# DC-DC_5V0_To_3V3.net
KiCad netlist of a schematic drawn in Altium Designer
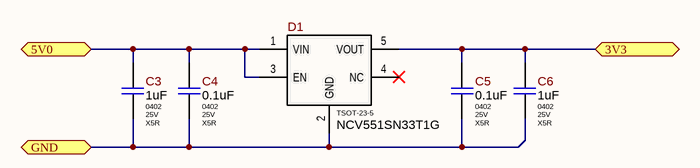
[diagram p0: DC-DC_5V0_To_3V3.SchDoc]

(export (version "E")
  (design (tool "Eeschema 10.0.6"))
  (components
    (comp (ref "C3")
      (value "1uF")
      (footprint "C_CERAMIC_0402_MED")
      (description "1uF 25V Х5R ±10% 0402 Ceramic Capacitor RoHS")
      (fields
        (field (name "PACKAGE") "0402")
        (field (name "VOLTAGE") "25V")
        (field (name "DIELECTRIC TYPE") "X5R")
        (field (name "PART NUMBER") "GRM155R61E105KA12D")
        (field (name "MANUFACTURER") "Murata Electronics")
      )
      (libsource (lib "EL.XXX.T01") (part "Capacitor-NonPolar"))
    )
    (comp (ref "C4")
      (value "0.1uF")
      (footprint "C_CERAMIC_0402_MED")
      (description "100nF 25V X5R ±10% 0402 Ceramic Capacitor RoHS")
      (fields
        (field (name "PACKAGE") "0402")
        (field (name "VOLTAGE") "25V")
        (field (name "DIELECTRIC TYPE") "X5R")
        (field (name "PART NUMBER") "CL05A104KA5NNNC")
        (field (name "MANUFACTURER") "Samsung Electro-Mechanics")
      )
      (libsource (lib "EL.XXX.T01") (part "Capacitor-NonPolar"))
    )
    (comp (ref "C5")
      (value "0.1uF")
      (footprint "C_CERAMIC_0402_MED")
      (description "100nF 25V X5R ±10% 0402 Ceramic Capacitor RoHS")
      (fields
        (field (name "PACKAGE") "0402")
        (field (name "VOLTAGE") "25V")
        (field (name "DIELECTRIC TYPE") "X5R")
        (field (name "PART NUMBER") "CL05A104KA5NNNC")
        (field (name "MANUFACTURER") "Samsung Electro-Mechanics")
      )
      (libsource (lib "EL.XXX.T01") (part "Capacitor-NonPolar"))
    )
    (comp (ref "C6")
      (value "1uF")
      (footprint "C_CERAMIC_0402_MED")
      (description "1uF 25V Х5R ±10% 0402 Ceramic Capacitor RoHS")
      (fields
        (field (name "PACKAGE") "0402")
        (field (name "VOLTAGE") "25V")
        (field (name "DIELECTRIC TYPE") "X5R")
        (field (name "PART NUMBER") "GRM155R61E105KA12D")
        (field (name "MANUFACTURER") "Murata Electronics")
      )
      (libsource (lib "EL.XXX.T01") (part "Capacitor-NonPolar"))
    )
    (comp (ref "D1")
      (value "NCV551SN33T1G")
      (footprint "TSOT-23-5")
      (description "Fixed 3.3V, 150mA Output, 12V max Input, 4uA Iq, LDO, TSOT-23-5")
      (fields
        (field (name "PACKAGE") "TSOT-23-5")
        (field (name "PART NUMBER") "NCV551SN33T1G")
        (field (name "MANUFACTURER") "Onsemi")
      )
      (libsource (lib "EL.XXX.T01") (part "NCV551SNxxT1G"))
    )
  )
  (nets
    (net (code "1") (name "/3V3") (class "Default")
      (node (ref "C5") (pin "1") (pinfunction "1_1") (pintype "passive"))
      (node (ref "C6") (pin "1") (pinfunction "1_1") (pintype "passive"))
      (node (ref "D1") (pin "5") (pinfunction "VOUT_5") (pintype "passive"))
    )
    (net (code "2") (name "/5V0") (class "Default")
      (node (ref "C3") (pin "1") (pinfunction "1_1") (pintype "passive"))
      (node (ref "C4") (pin "1") (pinfunction "1_1") (pintype "passive"))
      (node (ref "D1") (pin "1") (pinfunction "VIN_1") (pintype "passive"))
      (node (ref "D1") (pin "3") (pinfunction "EN_3") (pintype "passive"))
    )
    (net (code "3") (name "/GND") (class "Default")
      (node (ref "C3") (pin "2") (pinfunction "2_2") (pintype "passive"))
      (node (ref "C4") (pin "2") (pinfunction "2_2") (pintype "passive"))
      (node (ref "C5") (pin "2") (pinfunction "2_2") (pintype "passive"))
      (node (ref "C6") (pin "2") (pinfunction "2_2") (pintype "passive"))
      (node (ref "D1") (pin "2") (pinfunction "GND_2") (pintype "passive"))
    )
    (net (code "4") (name "unconnected-(D1-NC-Pad4)") (class "Default")
      (node (ref "D1") (pin "4") (pinfunction "NC_4") (pintype "passive+no_connect"))
    )
  )
)
